# SCFschem.net
KiCad netlist of a schematic drawn in EAGLE
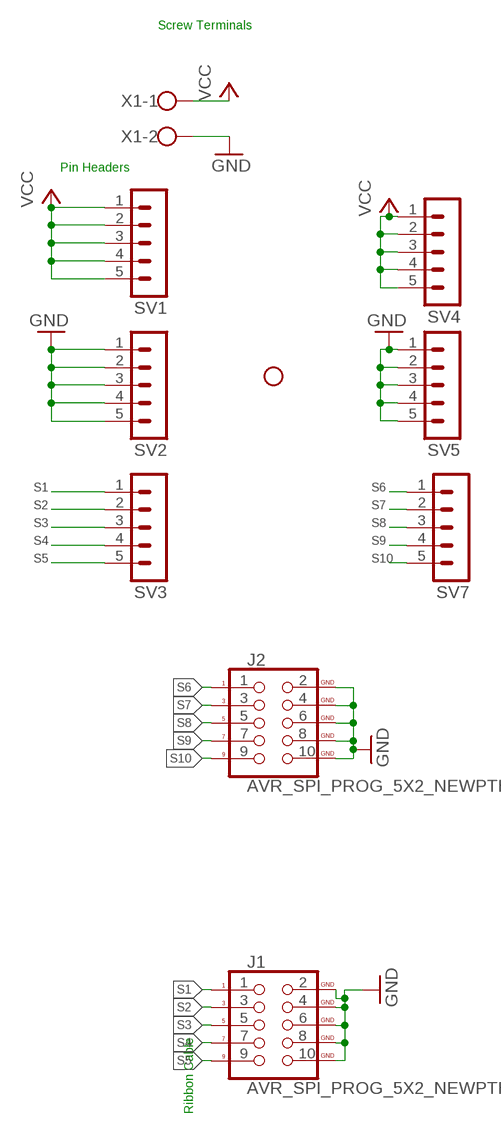
[diagram p0: schematic, sheet 1]

(export (version "E")
  (design (tool "Eeschema 10.0.6"))
  (components
    (comp (ref "H1")
      (value "STAND-OFF-NEWNEW")
      (footprint "eagle-import:STAND-OFF-NEW")
      (libsource (lib "eagle-import") (part "STAND-OFF-NEWNEW"))
    )
    (comp (ref "J1")
      (value "AVR_SPI_PROG_5X2_NEWPTH2")
      (footprint "eagle-import:2X5-SHROUDED")
      (libsource (lib "eagle-import") (part "AVR_SPI_PROG_5X2_NEWPTH2"))
    )
    (comp (ref "J2")
      (value "AVR_SPI_PROG_5X2_NEWPTH2")
      (footprint "eagle-import:2X5-SHROUDED")
      (libsource (lib "eagle-import") (part "AVR_SPI_PROG_5X2_NEWPTH2"))
    )
    (comp (ref "SV1")
      (value "MA05-1")
      (footprint "eagle-import:MA05-1")
      (libsource (lib "eagle-import") (part "MA05-1"))
    )
    (comp (ref "SV2")
      (value "MA05-1")
      (footprint "eagle-import:MA05-1")
      (libsource (lib "eagle-import") (part "MA05-1"))
    )
    (comp (ref "SV3")
      (value "MA05-1")
      (footprint "eagle-import:MA05-1")
      (libsource (lib "eagle-import") (part "MA05-1"))
    )
    (comp (ref "SV4")
      (value "MA05-1")
      (footprint "eagle-import:MA05-1")
      (libsource (lib "eagle-import") (part "MA05-1"))
    )
    (comp (ref "SV5")
      (value "MA05-1")
      (footprint "eagle-import:MA05-1")
      (libsource (lib "eagle-import") (part "MA05-1"))
    )
    (comp (ref "SV7")
      (value "MA05-1")
      (footprint "eagle-import:MA05-1")
      (libsource (lib "eagle-import") (part "MA05-1"))
    )
    (comp (ref "X1")
      (value "1X02_5MM_SCREW")
      (footprint "eagle-import:W237-102")
      (fields (field (name "MPN") "237-102"))
      (libsource (lib "eagle-import") (part "1X02_5MM_SCREW"))
    )
  )
  (nets
    (net (code "1") (name "GND") (class "Default")
      (node (ref "J1") (pin "10") (pinfunction "GND_10") (pintype "power_in"))
      (node (ref "J1") (pin "2") (pinfunction "GND_2") (pintype "power_in"))
      (node (ref "J1") (pin "4") (pinfunction "GND_4") (pintype "power_in"))
      (node (ref "J1") (pin "6") (pinfunction "GND_6") (pintype "power_in"))
      (node (ref "J1") (pin "8") (pinfunction "GND_8") (pintype "power_in"))
      (node (ref "J2") (pin "10") (pinfunction "GND_10") (pintype "power_in"))
      (node (ref "J2") (pin "2") (pinfunction "GND_2") (pintype "power_in"))
      (node (ref "J2") (pin "4") (pinfunction "GND_4") (pintype "power_in"))
      (node (ref "J2") (pin "6") (pinfunction "GND_6") (pintype "power_in"))
      (node (ref "J2") (pin "8") (pinfunction "GND_8") (pintype "power_in"))
      (node (ref "SV2") (pin "1") (pinfunction "1_1") (pintype "passive"))
      (node (ref "SV2") (pin "2") (pinfunction "2_2") (pintype "passive"))
      (node (ref "SV2") (pin "3") (pinfunction "3_3") (pintype "passive"))
      (node (ref "SV2") (pin "4") (pinfunction "4_4") (pintype "passive"))
      (node (ref "SV2") (pin "5") (pinfunction "5_5") (pintype "passive"))
      (node (ref "SV5") (pin "1") (pinfunction "1_1") (pintype "passive"))
      (node (ref "SV5") (pin "2") (pinfunction "2_2") (pintype "passive"))
      (node (ref "SV5") (pin "3") (pinfunction "3_3") (pintype "passive"))
      (node (ref "SV5") (pin "4") (pinfunction "4_4") (pintype "passive"))
      (node (ref "SV5") (pin "5") (pinfunction "5_5") (pintype "passive"))
      (node (ref "X1") (pin "2") (pinfunction "KL_2") (pintype "passive"))
    )
    (net (code "2") (name "S1") (class "Default")
      (node (ref "J1") (pin "1") (pinfunction "1_1") (pintype "passive"))
      (node (ref "SV3") (pin "1") (pinfunction "1_1") (pintype "passive"))
    )
    (net (code "3") (name "S2") (class "Default")
      (node (ref "J1") (pin "3") (pinfunction "3_3") (pintype "passive"))
      (node (ref "SV3") (pin "2") (pinfunction "2_2") (pintype "passive"))
    )
    (net (code "4") (name "S3") (class "Default")
      (node (ref "J1") (pin "5") (pinfunction "5_5") (pintype "passive"))
      (node (ref "SV3") (pin "3") (pinfunction "3_3") (pintype "passive"))
    )
    (net (code "5") (name "S4") (class "Default")
      (node (ref "J1") (pin "7") (pinfunction "7_7") (pintype "passive"))
      (node (ref "SV3") (pin "4") (pinfunction "4_4") (pintype "passive"))
    )
    (net (code "6") (name "S5") (class "Default")
      (node (ref "J1") (pin "9") (pinfunction "9_9") (pintype "passive"))
      (node (ref "SV3") (pin "5") (pinfunction "5_5") (pintype "passive"))
    )
    (net (code "7") (name "S6") (class "Default")
      (node (ref "J2") (pin "1") (pinfunction "1_1") (pintype "passive"))
      (node (ref "SV7") (pin "1") (pinfunction "1_1") (pintype "passive"))
    )
    (net (code "8") (name "S7") (class "Default")
      (node (ref "J2") (pin "3") (pinfunction "3_3") (pintype "passive"))
      (node (ref "SV7") (pin "2") (pinfunction "2_2") (pintype "passive"))
    )
    (net (code "9") (name "S8") (class "Default")
      (node (ref "J2") (pin "5") (pinfunction "5_5") (pintype "passive"))
      (node (ref "SV7") (pin "3") (pinfunction "3_3") (pintype "passive"))
    )
    (net (code "10") (name "S9") (class "Default")
      (node (ref "J2") (pin "7") (pinfunction "7_7") (pintype "passive"))
      (node (ref "SV7") (pin "4") (pinfunction "4_4") (pintype "passive"))
    )
    (net (code "11") (name "S10") (class "Default")
      (node (ref "J2") (pin "9") (pinfunction "9_9") (pintype "passive"))
      (node (ref "SV7") (pin "5") (pinfunction "5_5") (pintype "passive"))
    )
    (net (code "12") (name "VCC") (class "Default")
      (node (ref "SV1") (pin "1") (pinfunction "1_1") (pintype "passive"))
      (node (ref "SV1") (pin "2") (pinfunction "2_2") (pintype "passive"))
      (node (ref "SV1") (pin "3") (pinfunction "3_3") (pintype "passive"))
      (node (ref "SV1") (pin "4") (pinfunction "4_4") (pintype "passive"))
      (node (ref "SV1") (pin "5") (pinfunction "5_5") (pintype "passive"))
      (node (ref "SV4") (pin "1") (pinfunction "1_1") (pintype "passive"))
      (node (ref "SV4") (pin "2") (pinfunction "2_2") (pintype "passive"))
      (node (ref "SV4") (pin "3") (pinfunction "3_3") (pintype "passive"))
      (node (ref "SV4") (pin "4") (pinfunction "4_4") (pintype "passive"))
      (node (ref "SV4") (pin "5") (pinfunction "5_5") (pintype "passive"))
      (node (ref "X1") (pin "1") (pinfunction "KL_1") (pintype "passive"))
    )
  )
)
